# Source_Select.net
KiCad netlist of a schematic drawn in Altium Designer
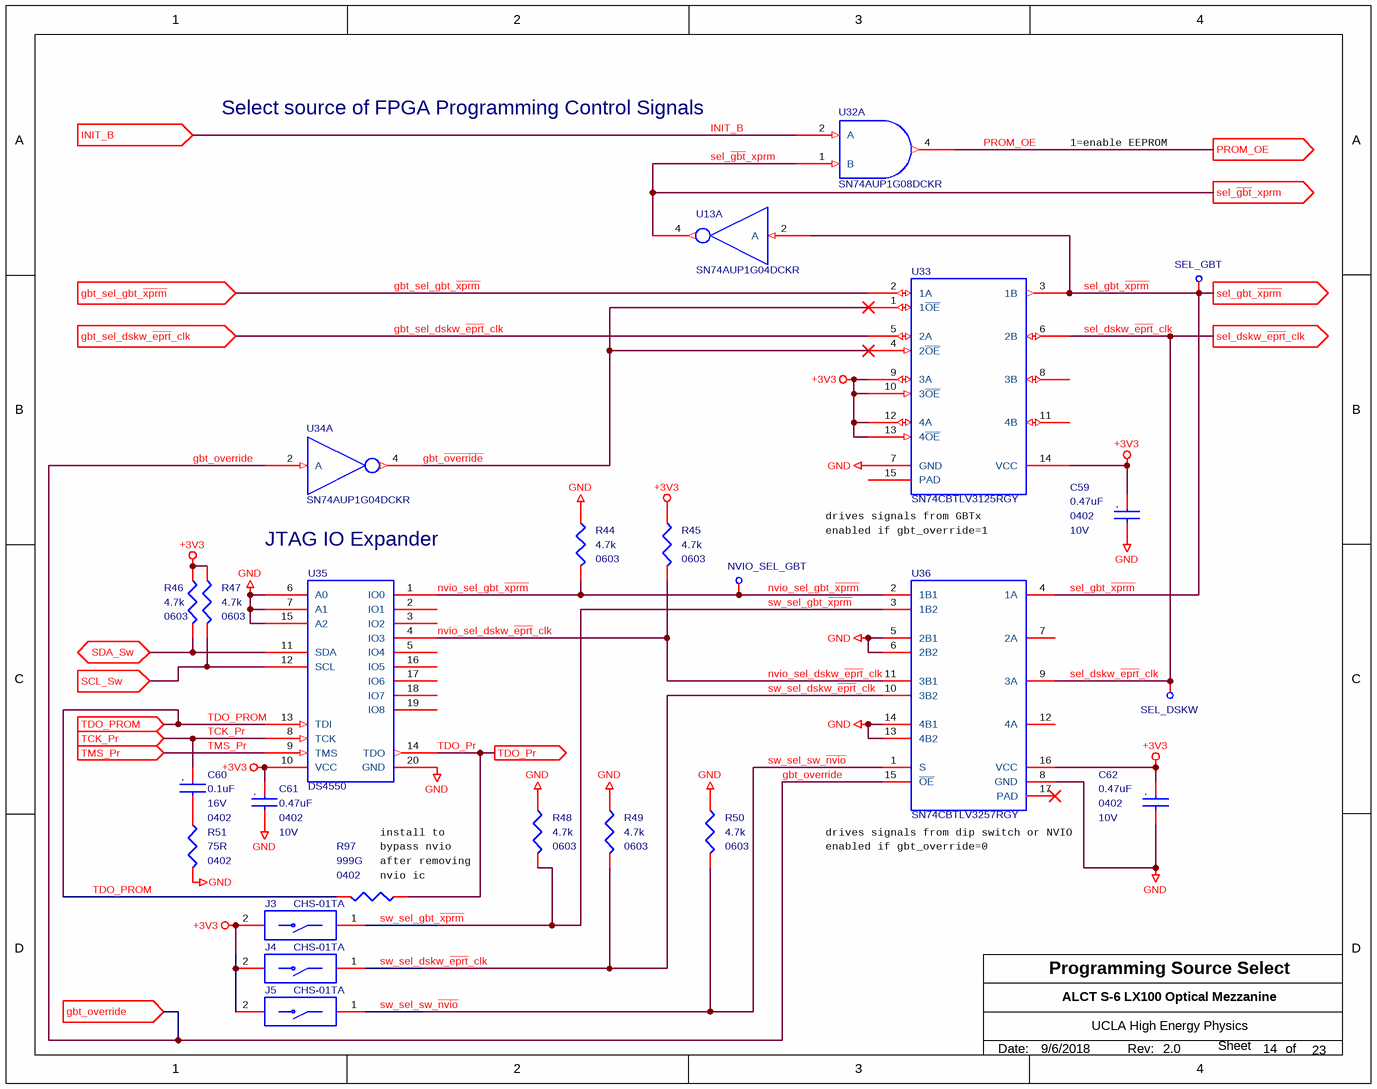
[diagram p0: Source_Select.SchDoc]

(export (version "E")
  (design (tool "Eeschema 10.0.6"))
  (components
    (comp (ref "C59")
      (value "0.47uF")
      (footprint "MC_S6/SM/C_0402_IPC")
      (description "CAP CER 0.47UF 10V X5R 0402")
      (fields
        (field (name "MANUFACTURER") "Murata Electronics North America")
        (field (name "MANUFACTURER PART NUMBER") "GRM155R61A474KE15D")
        (field (name "VOLTAGE - RATED") "10V")
        (field (name "PACKAGE") "0402")
      )
      (libsource (lib "ALCT_MEZ_SPARTAN6_Library") (part "GRM155R61A474KE15D"))
    )
    (comp (ref "C60")
      (value "0.1uF")
      (footprint "MC_S6/SM/C_0402_IPC")
      (description "CAP CER 0.1UF 16V X7R 0402")
      (fields
        (field (name "MANUFACTURER") "KEMET")
        (field (name "MANUFACTURER PART NUMBER") "C0402C104K4RACTU")
        (field (name "PACKAGE") "0402")
        (field (name "VOLTAGE - RATED") "16V")
      )
      (libsource (lib "ALCT_MEZ_SPARTAN6_Library") (part "C0402C104K4RACTU"))
    )
    (comp (ref "C61")
      (value "0.47uF")
      (footprint "MC_S6/SM/C_0402_IPC")
      (description "CAP CER 0.47UF 10V X5R 0402")
      (fields
        (field (name "MANUFACTURER") "Murata Electronics North America")
        (field (name "MANUFACTURER PART NUMBER") "GRM155R61A474KE15D")
        (field (name "VOLTAGE - RATED") "10V")
        (field (name "PACKAGE") "0402")
      )
      (libsource (lib "ALCT_MEZ_SPARTAN6_Library") (part "GRM155R61A474KE15D"))
    )
    (comp (ref "C62")
      (value "0.47uF")
      (footprint "MC_S6/SM/C_0402_IPC")
      (description "CAP CER 0.47UF 10V X5R 0402")
      (fields
        (field (name "MANUFACTURER") "Murata Electronics North America")
        (field (name "MANUFACTURER PART NUMBER") "GRM155R61A474KE15D")
        (field (name "VOLTAGE - RATED") "10V")
        (field (name "PACKAGE") "0402")
      )
      (libsource (lib "ALCT_MEZ_SPARTAN6_Library") (part "GRM155R61A474KE15D"))
    )
    (comp (ref "J3")
      (value "CHS-01TA")
      (footprint "CHS-01TA")
      (description "SWITCH SLIDE DIP SPST 100MA 6V")
      (fields (field (name "MANUFACTURER") "Nidec Copal"))
      (libsource (lib "ALCT_MEZ_SPARTAN6_Library") (part "CHS-01TA"))
    )
    (comp (ref "J4")
      (value "CHS-01TA")
      (footprint "CHS-01TA")
      (description "SWITCH SLIDE DIP SPST 100MA 6V")
      (fields (field (name "MANUFACTURER") "Nidec Copal"))
      (libsource (lib "ALCT_MEZ_SPARTAN6_Library") (part "CHS-01TA"))
    )
    (comp (ref "J5")
      (value "CHS-01TA")
      (footprint "CHS-01TA")
      (description "SWITCH SLIDE DIP SPST 100MA 6V")
      (fields (field (name "MANUFACTURER") "Nidec Copal"))
      (libsource (lib "ALCT_MEZ_SPARTAN6_Library") (part "CHS-01TA"))
    )
    (comp (ref "NVIO_SEL_GBT")
      (value "Test Point Via")
      (footprint "MC_S6/TH/TPVIA")
      (libsource (lib "ALCT_MEZ_SPARTAN6_Library") (part "TPVIA"))
    )
    (comp (ref "R44")
      (value "4.7k")
      (footprint "MC_S6/SM/R_0603_IPC")
      (description "RES SMD 4.7K OHM 1% 1/10W 0603")
      (fields
        (field (name "TOLERANCE") "±1%")
        (field (name "MANUFACTURER") "Bourns Inc.")
        (field (name "SUPPLIER DEVICE PACKAGE") "0603")
      )
      (libsource (lib "ALCT_MEZ_SPARTAN6_Library") (part "CR0603-FX-4701ELF"))
    )
    (comp (ref "R45")
      (value "4.7k")
      (footprint "MC_S6/SM/R_0603_IPC")
      (description "RES SMD 4.7K OHM 1% 1/10W 0603")
      (fields
        (field (name "TOLERANCE") "±1%")
        (field (name "MANUFACTURER") "Bourns Inc.")
        (field (name "SUPPLIER DEVICE PACKAGE") "0603")
      )
      (libsource (lib "ALCT_MEZ_SPARTAN6_Library") (part "CR0603-FX-4701ELF"))
    )
    (comp (ref "R46")
      (value "4.7k")
      (footprint "MC_S6/SM/R_0603_IPC")
      (description "RES SMD 4.7K OHM 1% 1/10W 0603")
      (fields
        (field (name "TOLERANCE") "±1%")
        (field (name "MANUFACTURER") "Bourns Inc.")
        (field (name "SUPPLIER DEVICE PACKAGE") "0603")
      )
      (libsource (lib "ALCT_MEZ_SPARTAN6_Library") (part "CR0603-FX-4701ELF"))
    )
    (comp (ref "R47")
      (value "4.7k")
      (footprint "MC_S6/SM/R_0603_IPC")
      (description "RES SMD 4.7K OHM 1% 1/10W 0603")
      (fields
        (field (name "TOLERANCE") "±1%")
        (field (name "MANUFACTURER") "Bourns Inc.")
        (field (name "SUPPLIER DEVICE PACKAGE") "0603")
      )
      (libsource (lib "ALCT_MEZ_SPARTAN6_Library") (part "CR0603-FX-4701ELF"))
    )
    (comp (ref "R48")
      (value "4.7k")
      (footprint "MC_S6/SM/R_0603_IPC")
      (description "RES SMD 4.7K OHM 1% 1/10W 0603")
      (fields
        (field (name "TOLERANCE") "±1%")
        (field (name "MANUFACTURER") "Bourns Inc.")
        (field (name "SUPPLIER DEVICE PACKAGE") "0603")
      )
      (libsource (lib "ALCT_MEZ_SPARTAN6_Library") (part "CR0603-FX-4701ELF"))
    )
    (comp (ref "R49")
      (value "4.7k")
      (footprint "MC_S6/SM/R_0603_IPC")
      (description "RES SMD 4.7K OHM 1% 1/10W 0603")
      (fields
        (field (name "TOLERANCE") "±1%")
        (field (name "MANUFACTURER") "Bourns Inc.")
        (field (name "SUPPLIER DEVICE PACKAGE") "0603")
      )
      (libsource (lib "ALCT_MEZ_SPARTAN6_Library") (part "CR0603-FX-4701ELF"))
    )
    (comp (ref "R50")
      (value "4.7k")
      (footprint "MC_S6/SM/R_0603_IPC")
      (description "RES SMD 4.7K OHM 1% 1/10W 0603")
      (fields
        (field (name "TOLERANCE") "±1%")
        (field (name "MANUFACTURER") "Bourns Inc.")
        (field (name "SUPPLIER DEVICE PACKAGE") "0603")
      )
      (libsource (lib "ALCT_MEZ_SPARTAN6_Library") (part "CR0603-FX-4701ELF"))
    )
    (comp (ref "R51")
      (value "75R")
      (footprint "MC_S6/SM/R_0402_IPC")
      (description "RES SMD 75 OHM 5% 1/10W 0402")
      (fields
        (field (name "TOLERANCE") "±5%")
        (field (name "MANUFACTURER") "Panasonic Electronic Components")
        (field (name "SUPPLIER DEVICE PACKAGE") "0402")
      )
      (libsource (lib "ALCT_MEZ_SPARTAN6_Library") (part "ERJ-2GEJ750X"))
    )
    (comp (ref "R97")
      (value "999G")
      (footprint "MC_S6/SM/R_0402_IPC")
      (description "RES SMD 999G OHM 5% 1/16W 0402")
      (fields
        (field (name "MANUFACTURER PART NUMBER") "Do Not Place")
        (field (name "SUPPLIER DEVICE PACKAGE") "0402")
      )
      (libsource (lib "ALCT_MEZ_SPARTAN6_Library") (part "RES999G 0402"))
    )
    (comp (ref "SEL_DSKW")
      (value "Test Point Via")
      (footprint "MC_S6/TH/TPVIA")
      (libsource (lib "ALCT_MEZ_SPARTAN6_Library") (part "TPVIA"))
    )
    (comp (ref "SEL_GBT")
      (value "Test Point Via")
      (footprint "MC_S6/TH/TPVIA")
      (libsource (lib "ALCT_MEZ_SPARTAN6_Library") (part "TPVIA"))
    )
    (comp (ref "U13")
      (value "SN74AUP1G04DCKR")
      (footprint "MC_S6/SM/SOT_SC70_DCK5")
      (description "IC INVERTER LP 5TSSOP")
      (fields (field (name "MANUFACTURER") "Texas Instruments"))
      (libsource (lib "") (part "SN74AUP1G04DCKR_1"))
    )
    (comp (ref "U32")
      (value "SN74AUP1G08DCKR")
      (footprint "MC_S6/SM/SOT_SC70_DCK5")
      (description "IC GATE AND 1CH 2-INP 5-TSSOP")
      (fields
        (field (name "MANUFACTURER") "Texas Instruments")
        (field (name "MANUFACTURER PART NUMBER") "SN74AUP1G08DCKT")
      )
      (libsource (lib "ALCT_MEZ_SPARTAN6_Library") (part "SN74AUP1G08DCKR"))
    )
    (comp (ref "U33")
      (value "SN74CBTLV3125RGY")
      (footprint "S-PVQFN-N14")
      (description "IC 4 BIT FET BUS SWITCH, QFN-14")
      (fields
        (field (name "MANUFACTURER") "Texas Instruments")
        (field (name "MANUFACTURER PART NUMBER") "SN74CBTLV3125RGYR")
      )
      (libsource (lib "ALCT_MEZ_SPARTAN6_Library") (part "SN74CBTLV3125RGY"))
    )
    (comp (ref "U34")
      (value "SN74AUP1G04DCKR")
      (footprint "MC_S6/SM/SOT_SC70_DCK5")
      (description "IC INVERTER LP 5TSSOP")
      (fields (field (name "MANUFACTURER") "Texas Instruments"))
      (libsource (lib "ALCT_MEZ_SPARTAN6_Library") (part "SN74AUP1G04DCKR"))
    )
    (comp (ref "U35")
      (value "DS4550")
      (footprint "TSSOP-20")
      (description "IC I/O EXPANDER I2C 9B 20TSSOP")
      (fields (field (name "MANUFACTURER") "Maxim") (field (name "MANUFACTURER PART NUMBER") "DS4550E+"))
      (libsource (lib "ALCT_MEZ_SPARTAN6_Library") (part "DS4550"))
    )
    (comp (ref "U36")
      (value "SN74CBTLV3257RGY")
      (footprint "R-PVQFN-N16")
      (description "IC 4 BIT FET BUS SWITCH, VQFN-16")
      (fields
        (field (name "MANUFACTURER") "Texas Instruments")
        (field (name "MANUFACTURER PART NUMBER") "SN74CBTLV3257RGYR")
      )
      (libsource (lib "ALCT_MEZ_SPARTAN6_Library") (part "SN74CBTLV3257RGY"))
    )
  )
  (nets
    (net (code "1") (name "+3V3") (class "Default")
      (node (ref "C59") (pin "1") (pinfunction "1_1") (pintype "passive"))
      (node (ref "C61") (pin "1") (pinfunction "1_1") (pintype "passive"))
      (node (ref "C62") (pin "1") (pinfunction "1_1") (pintype "passive"))
      (node (ref "J3") (pin "2") (pinfunction "2_2") (pintype "passive"))
      (node (ref "J4") (pin "2") (pinfunction "2_2") (pintype "passive"))
      (node (ref "J5") (pin "2") (pinfunction "2_2") (pintype "passive"))
      (node (ref "R45") (pin "1") (pinfunction "1_1") (pintype "passive"))
      (node (ref "R46") (pin "1") (pinfunction "1_1") (pintype "passive"))
      (node (ref "R47") (pin "1") (pinfunction "1_1") (pintype "passive"))
      (node (ref "U33") (pin "10") (pinfunction "3~{OE}_10") (pintype "input"))
      (node (ref "U33") (pin "12") (pinfunction "4A_12") (pintype "bidirectional"))
      (node (ref "U33") (pin "13") (pinfunction "4~{OE}_13") (pintype "input"))
      (node (ref "U33") (pin "14") (pinfunction "VCC_14") (pintype "power_in"))
      (node (ref "U33") (pin "9") (pinfunction "3A_9") (pintype "bidirectional"))
      (node (ref "U35") (pin "10") (pinfunction "VCC_10") (pintype "passive"))
      (node (ref "U36") (pin "16") (pinfunction "VCC_16") (pintype "passive"))
    )
    (net (code "2") (name "/INIT_B") (class "Default")
      (node (ref "U32") (pin "2") (pinfunction "A_2") (pintype "input"))
    )
    (net (code "3") (name "/PROM_OE") (class "Default")
      (node (ref "U32") (pin "4") (pinfunction "Y_4") (pintype "output"))
    )
    (net (code "4") (name "/SCL_Sw") (class "Default")
      (node (ref "R47") (pin "2") (pinfunction "2_2") (pintype "passive"))
      (node (ref "U35") (pin "12") (pinfunction "SCL_12") (pintype "passive"))
    )
    (net (code "5") (name "/SDA_Sw") (class "Default")
      (node (ref "R46") (pin "2") (pinfunction "2_2") (pintype "passive"))
      (node (ref "U35") (pin "11") (pinfunction "SDA_11") (pintype "passive"))
    )
    (net (code "6") (name "/TCK_Pr") (class "Default")
      (node (ref "C60") (pin "1") (pinfunction "1_1") (pintype "passive"))
      (node (ref "U35") (pin "8") (pinfunction "TCK_8") (pintype "input"))
    )
    (net (code "7") (name "/TDO_PROM") (class "Default")
      (node (ref "R97") (pin "2") (pinfunction "2_2") (pintype "passive"))
      (node (ref "U35") (pin "13") (pinfunction "TDI_13") (pintype "input"))
    )
    (net (code "8") (name "/TDO_Pr") (class "Default")
      (node (ref "R97") (pin "1") (pinfunction "1_1") (pintype "passive"))
      (node (ref "U35") (pin "14") (pinfunction "TDO_14") (pintype "output"))
    )
    (net (code "9") (name "/TMS_Pr") (class "Default")
      (node (ref "U35") (pin "9") (pinfunction "TMS_9") (pintype "input"))
    )
    (net (code "10") (name "/gbt_override") (class "Default")
      (node (ref "U34") (pin "2") (pinfunction "A_2") (pintype "input"))
      (node (ref "U36") (pin "15") (pinfunction "~{OE}_15") (pintype "passive"))
    )
    (net (code "11") (name "/gbt_sel_dskw_~{eprt}_clk") (class "Default")
      (node (ref "U33") (pin "5") (pinfunction "2A_5") (pintype "bidirectional"))
    )
    (net (code "12") (name "/gbt_sel_gbt_~{xprm}") (class "Default")
      (node (ref "U33") (pin "2") (pinfunction "1A_2") (pintype "bidirectional"))
    )
    (net (code "13") (name "/gbt_~{override}") (class "Default")
      (node (ref "U33") (pin "1") (pinfunction "1~{OE}_1") (pintype "bidirectional"))
      (node (ref "U33") (pin "4") (pinfunction "2~{OE}_4") (pintype "input"))
      (node (ref "U34") (pin "4") (pinfunction "Y_4") (pintype "output"))
    )
    (net (code "14") (name "/nvio_sel_dskw_~{eprt}_clk") (class "Default")
      (node (ref "R45") (pin "2") (pinfunction "2_2") (pintype "passive"))
      (node (ref "U35") (pin "4") (pinfunction "IO3_4") (pintype "passive"))
      (node (ref "U36") (pin "11") (pinfunction "3B1_11") (pintype "passive"))
    )
    (net (code "15") (name "/nvio_sel_gbt_~{xprm}") (class "Default")
      (node (ref "NVIO_SEL_GBT") (pin "1") (pinfunction "In_1") (pintype "passive"))
      (node (ref "R44") (pin "2") (pinfunction "2_2") (pintype "passive"))
      (node (ref "U35") (pin "1") (pinfunction "IO0_1") (pintype "passive"))
      (node (ref "U36") (pin "2") (pinfunction "1B1_2") (pintype "passive"))
    )
    (net (code "16") (name "/sel_dskw_~{eprt}_clk") (class "Default")
      (node (ref "SEL_DSKW") (pin "1") (pinfunction "In_1") (pintype "passive"))
      (node (ref "U33") (pin "6") (pinfunction "2B_6") (pintype "bidirectional"))
      (node (ref "U36") (pin "9") (pinfunction "3A_9") (pintype "passive"))
    )
    (net (code "17") (name "/sel_gbt_~{xprm}") (class "Default")
      (node (ref "SEL_GBT") (pin "1") (pinfunction "In_1") (pintype "passive"))
      (node (ref "U13") (pin "2") (pinfunction "A_2") (pintype "input"))
      (node (ref "U33") (pin "3") (pinfunction "1B_3") (pintype "output"))
      (node (ref "U36") (pin "4") (pinfunction "1A_4") (pintype "passive"))
    )
    (net (code "18") (name "/sel_~{gbt}_xprm") (class "Default")
      (node (ref "U13") (pin "4") (pinfunction "Y_4") (pintype "output"))
      (node (ref "U32") (pin "1") (pinfunction "B_1") (pintype "input"))
    )
    (net (code "19") (name "/sw_sel_dskw_~{eprt}_clk") (class "Default")
      (node (ref "J4") (pin "1") (pinfunction "1_1") (pintype "passive"))
      (node (ref "R49") (pin "2") (pinfunction "2_2") (pintype "passive"))
      (node (ref "U36") (pin "10") (pinfunction "3B2_10") (pintype "passive"))
    )
    (net (code "20") (name "/sw_sel_gbt_~{xprm}") (class "Default")
      (node (ref "J3") (pin "1") (pinfunction "1_1") (pintype "passive"))
      (node (ref "R48") (pin "2") (pinfunction "2_2") (pintype "passive"))
      (node (ref "U36") (pin "3") (pinfunction "1B2_3") (pintype "passive"))
    )
    (net (code "21") (name "/sw_sel_sw_~{nvio}") (class "Default")
      (node (ref "J5") (pin "1") (pinfunction "1_1") (pintype "passive"))
      (node (ref "R50") (pin "2") (pinfunction "2_2") (pintype "passive"))
      (node (ref "U36") (pin "1") (pinfunction "S_1") (pintype "passive"))
    )
    (net (code "22") (name "GND") (class "Default")
      (node (ref "C59") (pin "2") (pinfunction "2_2") (pintype "passive"))
      (node (ref "C61") (pin "2") (pinfunction "2_2") (pintype "passive"))
      (node (ref "C62") (pin "2") (pinfunction "2_2") (pintype "passive"))
      (node (ref "R44") (pin "1") (pinfunction "1_1") (pintype "passive"))
      (node (ref "R48") (pin "1") (pinfunction "1_1") (pintype "passive"))
      (node (ref "R49") (pin "1") (pinfunction "1_1") (pintype "passive"))
      (node (ref "R50") (pin "1") (pinfunction "1_1") (pintype "passive"))
      (node (ref "R51") (pin "2") (pinfunction "2_2") (pintype "passive"))
      (node (ref "U33") (pin "7") (pinfunction "GND_7") (pintype "power_in"))
      (node (ref "U35") (pin "15") (pinfunction "A2_15") (pintype "passive"))
      (node (ref "U35") (pin "20") (pinfunction "GND_20") (pintype "passive"))
      (node (ref "U35") (pin "6") (pinfunction "A0_6") (pintype "passive"))
      (node (ref "U35") (pin "7") (pinfunction "A1_7") (pintype "passive"))
      (node (ref "U36") (pin "13") (pinfunction "4B2_13") (pintype "passive"))
      (node (ref "U36") (pin "14") (pinfunction "4B1_14") (pintype "passive"))
      (node (ref "U36") (pin "5") (pinfunction "2B1_5") (pintype "passive"))
      (node (ref "U36") (pin "6") (pinfunction "2B2_6") (pintype "passive"))
      (node (ref "U36") (pin "8") (pinfunction "GND_8") (pintype "passive"))
    )
    (net (code "23") (name "Net-(C60-Pad2)") (class "Default")
      (node (ref "C60") (pin "2") (pinfunction "2_2") (pintype "passive"))
      (node (ref "R51") (pin "1") (pinfunction "1_1") (pintype "passive"))
    )
    (net (code "24") (name "unconnected-(U33-3B-Pad8)") (class "Default")
      (node (ref "U33") (pin "8") (pinfunction "3B_8") (pintype "bidirectional"))
    )
    (net (code "25") (name "unconnected-(U33-4B-Pad11)") (class "Default")
      (node (ref "U33") (pin "11") (pinfunction "4B_11") (pintype "bidirectional"))
    )
    (net (code "26") (name "unconnected-(U33-PAD-Pad15)") (class "Default")
      (node (ref "U33") (pin "15") (pinfunction "PAD_15") (pintype "power_in"))
    )
    (net (code "27") (name "unconnected-(U35-IO1-Pad2)") (class "Default")
      (node (ref "U35") (pin "2") (pinfunction "IO1_2") (pintype "passive"))
    )
    (net (code "28") (name "unconnected-(U35-IO2-Pad3)") (class "Default")
      (node (ref "U35") (pin "3") (pinfunction "IO2_3") (pintype "passive"))
    )
    (net (code "29") (name "unconnected-(U35-IO4-Pad5)") (class "Default")
      (node (ref "U35") (pin "5") (pinfunction "IO4_5") (pintype "passive"))
    )
    (net (code "30") (name "unconnected-(U35-IO5-Pad16)") (class "Default")
      (node (ref "U35") (pin "16") (pinfunction "IO5_16") (pintype "passive"))
    )
    (net (code "31") (name "unconnected-(U35-IO6-Pad17)") (class "Default")
      (node (ref "U35") (pin "17") (pinfunction "IO6_17") (pintype "passive"))
    )
    (net (code "32") (name "unconnected-(U35-IO7-Pad18)") (class "Default")
      (node (ref "U35") (pin "18") (pinfunction "IO7_18") (pintype "passive"))
    )
    (net (code "33") (name "unconnected-(U35-IO8-Pad19)") (class "Default")
      (node (ref "U35") (pin "19") (pinfunction "IO8_19") (pintype "passive"))
    )
    (net (code "34") (name "unconnected-(U36-2A-Pad7)") (class "Default")
      (node (ref "U36") (pin "7") (pinfunction "2A_7") (pintype "passive"))
    )
    (net (code "35") (name "unconnected-(U36-4A-Pad12)") (class "Default")
      (node (ref "U36") (pin "12") (pinfunction "4A_12") (pintype "passive"))
    )
    (net (code "36") (name "unconnected-(U36-PAD-Pad17)") (class "Default")
      (node (ref "U36") (pin "17") (pinfunction "PAD_17") (pintype "passive+no_connect"))
    )
  )
)
